# GPIO_Expander2.net
KiCad netlist of a schematic drawn in Altium Designer
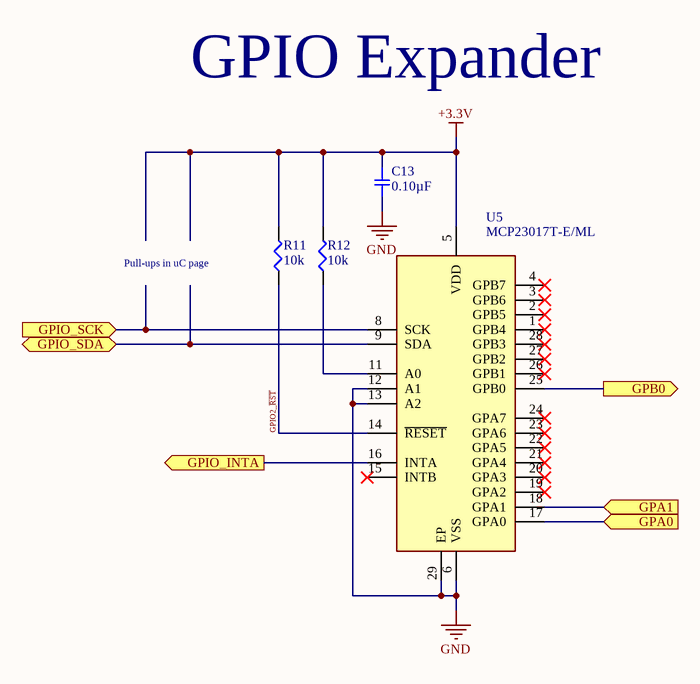
[diagram p0: GPIO_Expander2.SchDoc]

(export (version "E")
  (design (tool "Eeschema 10.0.6"))
  (components
    (comp (ref "C13")
      (value "0.10µF")
      (footprint "SMD-0402C")
      (description "CAP CER 0.1UF 16V X7R 0402")
      (fields
        (field (name "DIGI-KEY PART NUMBER") "490-4759-1-ND")
        (field (name "PART NUMBER") "GCM155R71C104KA55D")
      )
      (libsource (lib "capacitor_murata_0402") (part "GCM155R71C104KA55D"))
    )
    (comp (ref "R11")
      (value "10k")
      (footprint "SMD-0402-RES")
      (description "RES SMD 10K OHM 1% 1/10W 0402")
      (fields
        (field (name "PART NUMBER") "ERJ-2RKF1002X")
        (field (name "DIGI-KEY PART NUMBER") "P10.0KLCT-ND")
      )
      (libsource (lib "Panasonic_ERJ_0402") (part "ERJ-2RKF1002X"))
    )
    (comp (ref "R12")
      (value "10k")
      (footprint "SMD-0402-RES")
      (description "RES SMD 10K OHM 1% 1/10W 0402")
      (fields
        (field (name "PART NUMBER") "ERJ-2RKF1002X")
        (field (name "DIGI-KEY PART NUMBER") "P10.0KLCT-ND")
      )
      (libsource (lib "Panasonic_ERJ_0402") (part "ERJ-2RKF1002X"))
    )
    (comp (ref "U5")
      (value "MCP23017T-E/ML")
      (footprint "QFN65P600X600X100-29N-D")
      (description "Interface - I/O Expanders 16bit Input/Output Exp I2C interface")
      (fields (field (name "MOUSER PART NUMBER") "579-MCP23017T-E/ML"))
      (libsource (lib "SomoPowerPackControl") (part "MCP23017T-E/ML"))
    )
  )
  (nets
    (net (code "1") (name "+3.3V") (class "Default")
      (node (ref "C13") (pin "1") (pinfunction "1_1") (pintype "passive"))
      (node (ref "R11") (pin "2") (pinfunction "2_2") (pintype "passive"))
      (node (ref "R12") (pin "2") (pinfunction "2_2") (pintype "passive"))
      (node (ref "U5") (pin "5") (pinfunction "VDD_5") (pintype "passive"))
    )
    (net (code "2") (name "/GPA0") (class "Default")
      (node (ref "U5") (pin "17") (pinfunction "GPA0_17") (pintype "passive"))
    )
    (net (code "3") (name "/GPA1") (class "Default")
      (node (ref "U5") (pin "18") (pinfunction "GPA1_18") (pintype "passive"))
    )
    (net (code "4") (name "/GPB0") (class "Default")
      (node (ref "U5") (pin "25") (pinfunction "GPB0_25") (pintype "passive"))
    )
    (net (code "5") (name "/GPIO2_~{RST}") (class "Default")
      (node (ref "R11") (pin "1") (pinfunction "1_1") (pintype "passive"))
      (node (ref "U5") (pin "14") (pinfunction "~{RESET}_14") (pintype "passive"))
    )
    (net (code "6") (name "/GPIO_INTA") (class "Default")
      (node (ref "U5") (pin "16") (pinfunction "INTA_16") (pintype "passive"))
    )
    (net (code "7") (name "/GPIO_SCK") (class "Default")
      (node (ref "U5") (pin "8") (pinfunction "SCK_8") (pintype "passive"))
    )
    (net (code "8") (name "/GPIO_SDA") (class "Default")
      (node (ref "U5") (pin "9") (pinfunction "SDA_9") (pintype "passive"))
    )
    (net (code "9") (name "GND") (class "Default")
      (node (ref "C13") (pin "2") (pinfunction "2_2") (pintype "passive"))
      (node (ref "U5") (pin "12") (pinfunction "A1_12") (pintype "passive"))
      (node (ref "U5") (pin "13") (pinfunction "A2_13") (pintype "passive"))
      (node (ref "U5") (pin "29") (pinfunction "EP_29") (pintype "passive"))
      (node (ref "U5") (pin "6") (pinfunction "VSS_6") (pintype "passive"))
    )
    (net (code "10") (name "Net-(U5-A0)") (class "Default")
      (node (ref "R12") (pin "1") (pinfunction "1_1") (pintype "passive"))
      (node (ref "U5") (pin "11") (pinfunction "A0_11") (pintype "passive"))
    )
    (net (code "11") (name "unconnected-(U5-GPA2-Pad19)") (class "Default")
      (node (ref "U5") (pin "19") (pinfunction "GPA2_19") (pintype "passive+no_connect"))
    )
    (net (code "12") (name "unconnected-(U5-GPA3-Pad20)") (class "Default")
      (node (ref "U5") (pin "20") (pinfunction "GPA3_20") (pintype "passive+no_connect"))
    )
    (net (code "13") (name "unconnected-(U5-GPA4-Pad21)") (class "Default")
      (node (ref "U5") (pin "21") (pinfunction "GPA4_21") (pintype "passive+no_connect"))
    )
    (net (code "14") (name "unconnected-(U5-GPA5-Pad22)") (class "Default")
      (node (ref "U5") (pin "22") (pinfunction "GPA5_22") (pintype "passive+no_connect"))
    )
    (net (code "15") (name "unconnected-(U5-GPA6-Pad23)") (class "Default")
      (node (ref "U5") (pin "23") (pinfunction "GPA6_23") (pintype "passive+no_connect"))
    )
    (net (code "16") (name "unconnected-(U5-GPA7-Pad24)") (class "Default")
      (node (ref "U5") (pin "24") (pinfunction "GPA7_24") (pintype "passive+no_connect"))
    )
    (net (code "17") (name "unconnected-(U5-GPB1-Pad26)") (class "Default")
      (node (ref "U5") (pin "26") (pinfunction "GPB1_26") (pintype "passive+no_connect"))
    )
    (net (code "18") (name "unconnected-(U5-GPB2-Pad27)") (class "Default")
      (node (ref "U5") (pin "27") (pinfunction "GPB2_27") (pintype "passive+no_connect"))
    )
    (net (code "19") (name "unconnected-(U5-GPB3-Pad28)") (class "Default")
      (node (ref "U5") (pin "28") (pinfunction "GPB3_28") (pintype "passive+no_connect"))
    )
    (net (code "20") (name "unconnected-(U5-GPB4-Pad1)") (class "Default")
      (node (ref "U5") (pin "1") (pinfunction "GPB4_1") (pintype "passive+no_connect"))
    )
    (net (code "21") (name "unconnected-(U5-GPB5-Pad2)") (class "Default")
      (node (ref "U5") (pin "2") (pinfunction "GPB5_2") (pintype "passive+no_connect"))
    )
    (net (code "22") (name "unconnected-(U5-GPB6-Pad3)") (class "Default")
      (node (ref "U5") (pin "3") (pinfunction "GPB6_3") (pintype "passive+no_connect"))
    )
    (net (code "23") (name "unconnected-(U5-GPB7-Pad4)") (class "Default")
      (node (ref "U5") (pin "4") (pinfunction "GPB7_4") (pintype "passive+no_connect"))
    )
    (net (code "24") (name "unconnected-(U5-INTB-Pad15)") (class "Default")
      (node (ref "U5") (pin "15") (pinfunction "INTB_15") (pintype "passive+no_connect"))
    )
    (net (code "25") (name "unconnected-(U5-NC_1-Pad7)") (class "Default")
      (node (ref "U5") (pin "7") (pinfunction "NC_1_7") (pintype "passive"))
    )
    (net (code "26") (name "unconnected-(U5-NC_2-Pad10)") (class "Default")
      (node (ref "U5") (pin "10") (pinfunction "NC_2_10") (pintype "passive"))
    )
  )
)
